# SensorModule.net
KiCad netlist of a schematic drawn in EAGLE
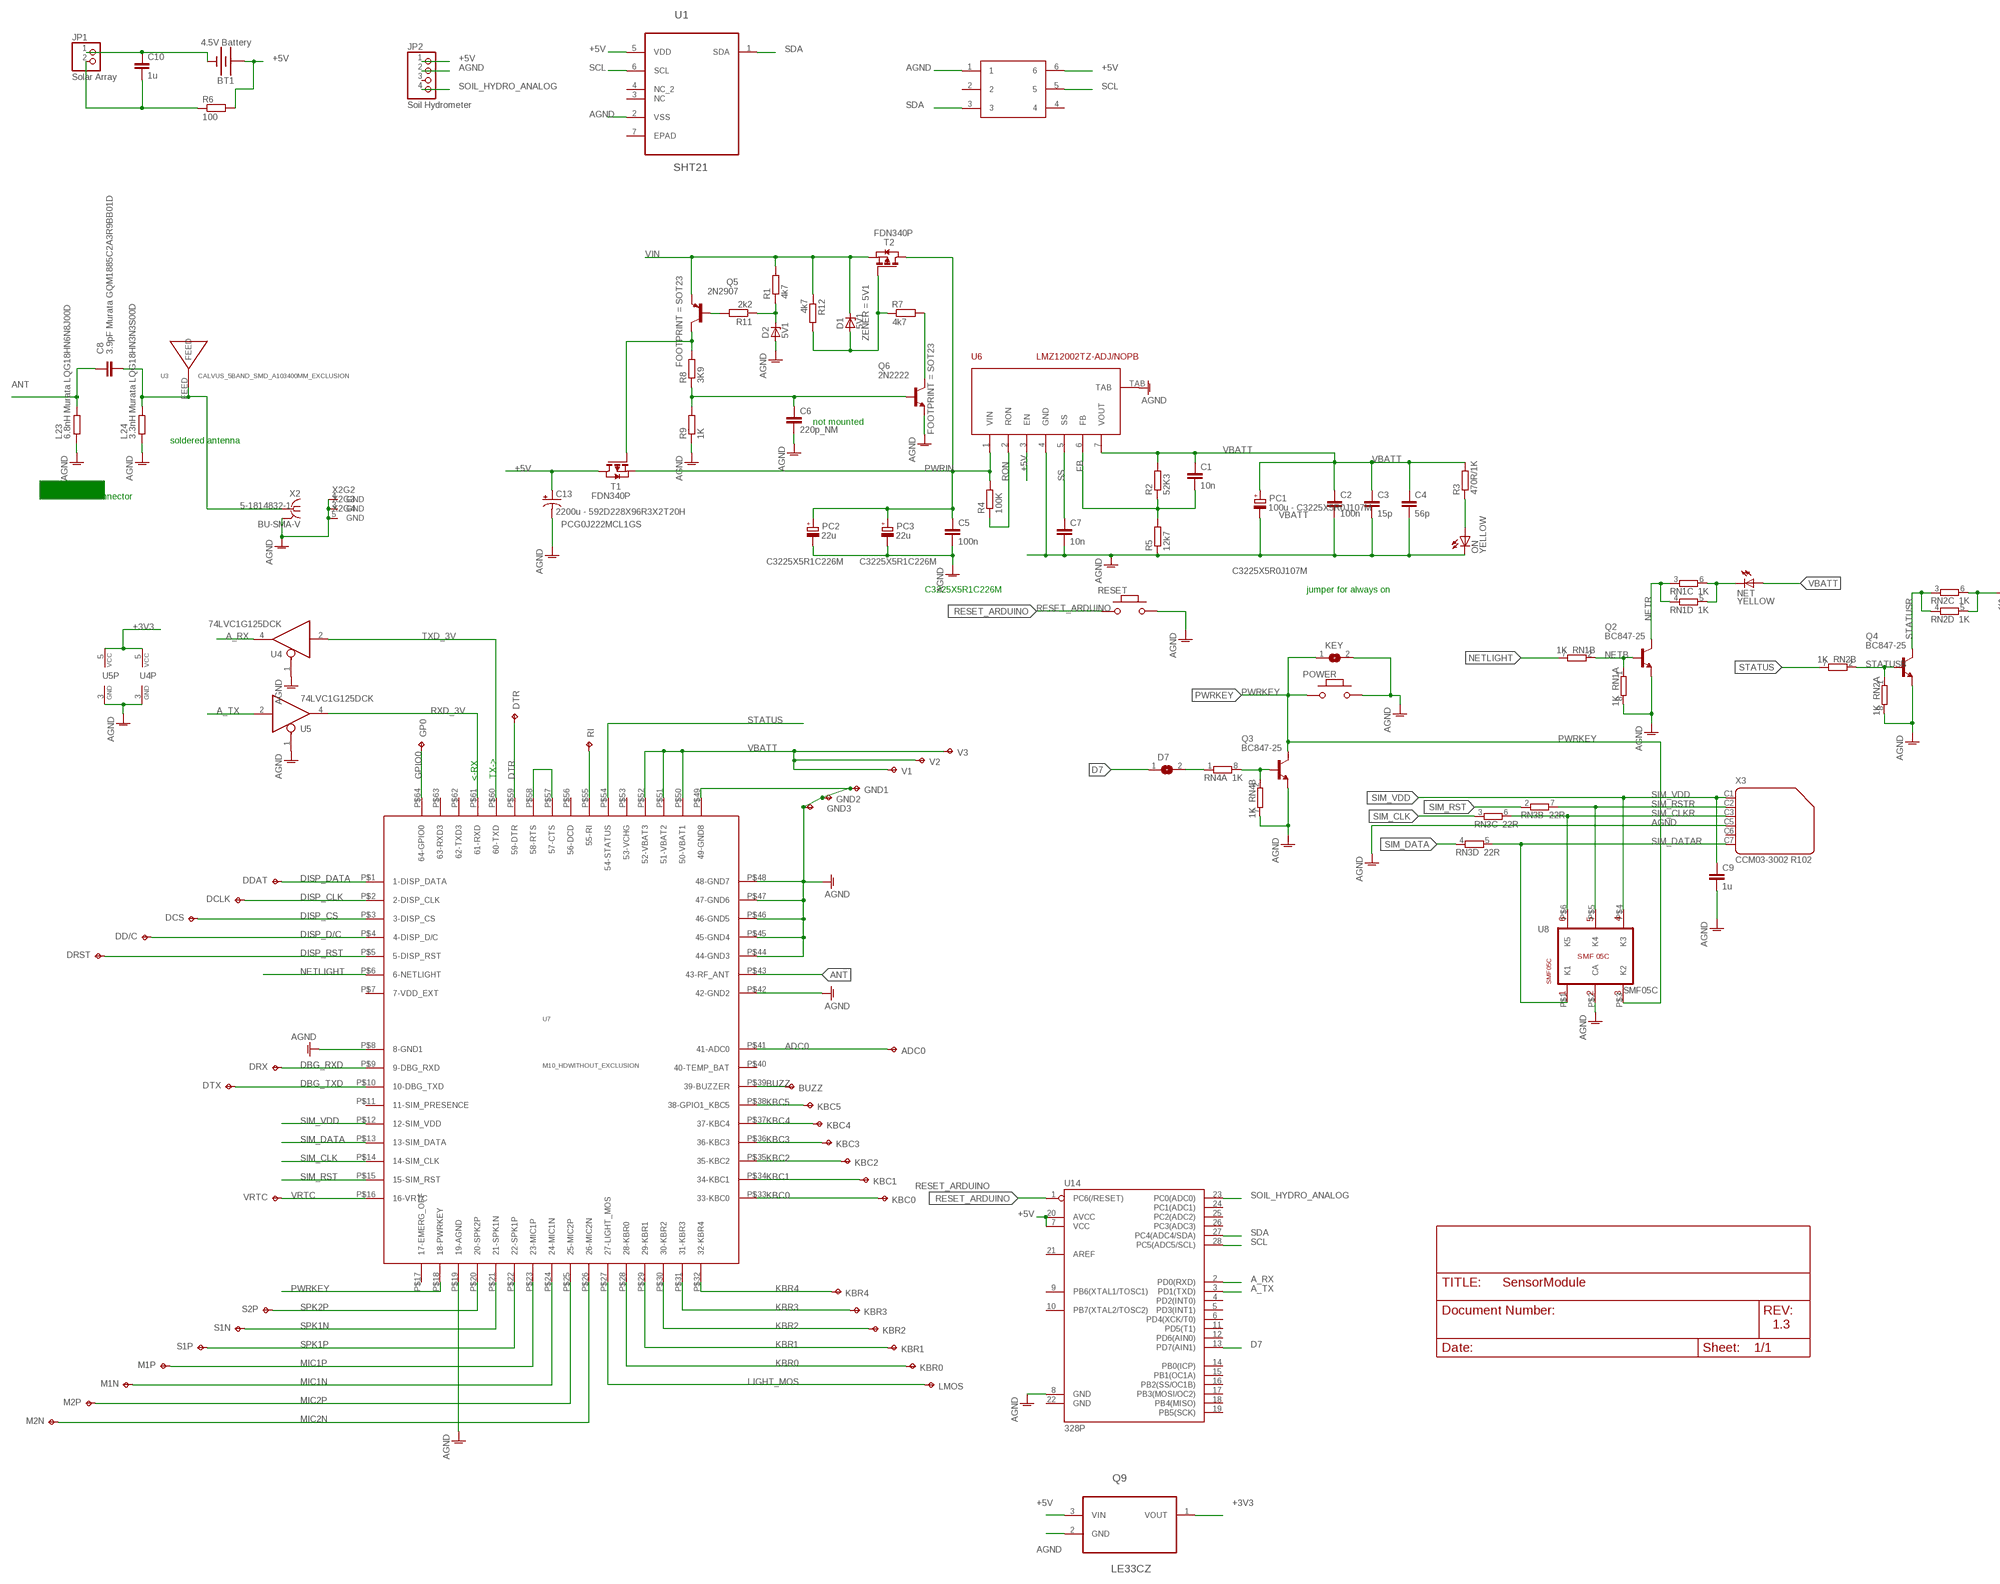
[diagram p0: schematic, sheet 1, part 1 of 2]
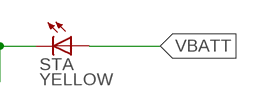
[diagram p1: schematic, sheet 1, part 2 of 2]

(export (version "E")
  (design (tool "Eeschema 10.0.6"))
  (components
    (comp (ref "ADC0")
      (value "TPPAD1-09")
      (footprint "eagle-import:P1-09")
      (libsource (lib "eagle-import") (part "TPPAD1-09"))
    )
    (comp (ref "BT1")
      (value "4.5V Battery")
      (footprint "eagle-import:BATTERY-AA")
      (libsource (lib "eagle-import") (part "BATTERY-AA"))
    )
    (comp (ref "BUZZ")
      (value "TPPAD1-09")
      (footprint "eagle-import:P1-09")
      (libsource (lib "eagle-import") (part "TPPAD1-09"))
    )
    (comp (ref "C1")
      (value "10n")
      (footprint "eagle-import:C0603-ROUND")
      (libsource (lib "eagle-import") (part "C-EU0603-RND"))
    )
    (comp (ref "C2")
      (value "100n")
      (footprint "eagle-import:C0603-ROUND")
      (libsource (lib "eagle-import") (part "C-EU0603-RND"))
    )
    (comp (ref "C3")
      (value "15p")
      (footprint "eagle-import:C0603-ROUND")
      (libsource (lib "eagle-import") (part "C-EU0603-RND"))
    )
    (comp (ref "C4")
      (value "56p")
      (footprint "eagle-import:C0603-ROUND")
      (libsource (lib "eagle-import") (part "C-EU0603-RND"))
    )
    (comp (ref "C5")
      (value "100n")
      (footprint "eagle-import:C0603-ROUND")
      (libsource (lib "eagle-import") (part "C-EU0603-RND"))
    )
    (comp (ref "C6")
      (value "220p_NM")
      (footprint "eagle-import:C0603-ROUND")
      (libsource (lib "eagle-import") (part "C-EU0603-RND"))
    )
    (comp (ref "C7")
      (value "10n")
      (footprint "eagle-import:C0603-ROUND")
      (libsource (lib "eagle-import") (part "C-EU0603-RND"))
    )
    (comp (ref "C8")
      (value "3.9pF Murata GQM1885C2A3R9BB01D")
      (footprint "eagle-import:C0603-ROUND")
      (libsource (lib "eagle-import") (part "C-EU0603-RND"))
    )
    (comp (ref "C9")
      (value "1u")
      (footprint "eagle-import:C0603-ROUND")
      (libsource (lib "eagle-import") (part "C-EU0603-RND"))
    )
    (comp (ref "C10")
      (value "1u")
      (footprint "eagle-import:C0201")
      (libsource (lib "eagle-import") (part "resistor_C-EUC0201"))
    )
    (comp (ref "C13")
      (value "2200u - 592D228X96R3X2T20H")
      (footprint "eagle-import:085CS_1AW")
      (libsource (lib "eagle-import") (part "CPOL-US085CS-1AW"))
    )
    (comp (ref "D1")
      (value "5V1")
      (footprint "eagle-import:SMB")
      (fields (field (name "ZENER") "5V1"))
      (libsource (lib "eagle-import") (part "ZENER-DIODESMB"))
    )
    (comp (ref "D2")
      (value "5V1")
      (footprint "eagle-import:SMB")
      (libsource (lib "eagle-import") (part "ZENER-DIODESMB"))
    )
    (comp (ref "D7") (value "SJ") (footprint "eagle-import:SJ") (libsource (lib "eagle-import") (part "SJ")))
    (comp (ref "DCLK")
      (value "TPPAD1-09")
      (footprint "eagle-import:P1-09")
      (libsource (lib "eagle-import") (part "TPPAD1-09"))
    )
    (comp (ref "DCS")
      (value "TPPAD1-09")
      (footprint "eagle-import:P1-09")
      (libsource (lib "eagle-import") (part "TPPAD1-09"))
    )
    (comp (ref "DD/C")
      (value "TPPAD1-09")
      (footprint "eagle-import:P1-09")
      (libsource (lib "eagle-import") (part "TPPAD1-09"))
    )
    (comp (ref "DDAT")
      (value "TPPAD1-09")
      (footprint "eagle-import:P1-09")
      (libsource (lib "eagle-import") (part "TPPAD1-09"))
    )
    (comp (ref "DRST")
      (value "TPPAD1-09")
      (footprint "eagle-import:P1-09")
      (libsource (lib "eagle-import") (part "TPPAD1-09"))
    )
    (comp (ref "DRX")
      (value "TPPAD1-09")
      (footprint "eagle-import:P1-09")
      (libsource (lib "eagle-import") (part "TPPAD1-09"))
    )
    (comp (ref "DTR")
      (value "TPPAD1-09")
      (footprint "eagle-import:P1-09")
      (libsource (lib "eagle-import") (part "TPPAD1-09"))
    )
    (comp (ref "DTX")
      (value "TPPAD1-09")
      (footprint "eagle-import:P1-09")
      (libsource (lib "eagle-import") (part "TPPAD1-09"))
    )
    (comp (ref "GND1")
      (value "TPPAD1-09")
      (footprint "eagle-import:P1-09")
      (libsource (lib "eagle-import") (part "TPPAD1-09"))
    )
    (comp (ref "GND2")
      (value "TPPAD1-09")
      (footprint "eagle-import:P1-09")
      (libsource (lib "eagle-import") (part "TPPAD1-09"))
    )
    (comp (ref "GND3")
      (value "TPPAD1-09")
      (footprint "eagle-import:P1-09")
      (libsource (lib "eagle-import") (part "TPPAD1-09"))
    )
    (comp (ref "GP0")
      (value "TPPAD1-09")
      (footprint "eagle-import:P1-09")
      (libsource (lib "eagle-import") (part "TPPAD1-09"))
    )
    (comp (ref "JP1")
      (value "Solar Array")
      (footprint "eagle-import:1X02")
      (libsource (lib "eagle-import") (part "PINHD-1X2"))
    )
    (comp (ref "JP2")
      (value "Soil Hydrometer")
      (footprint "eagle-import:1X04")
      (libsource (lib "eagle-import") (part "PINHD-1X4"))
    )
    (comp (ref "KBC0")
      (value "TPPAD1-09")
      (footprint "eagle-import:P1-09")
      (libsource (lib "eagle-import") (part "TPPAD1-09"))
    )
    (comp (ref "KBC1")
      (value "TPPAD1-09")
      (footprint "eagle-import:P1-09")
      (libsource (lib "eagle-import") (part "TPPAD1-09"))
    )
    (comp (ref "KBC2")
      (value "TPPAD1-09")
      (footprint "eagle-import:P1-09")
      (libsource (lib "eagle-import") (part "TPPAD1-09"))
    )
    (comp (ref "KBC3")
      (value "TPPAD1-09")
      (footprint "eagle-import:P1-09")
      (libsource (lib "eagle-import") (part "TPPAD1-09"))
    )
    (comp (ref "KBC4")
      (value "TPPAD1-09")
      (footprint "eagle-import:P1-09")
      (libsource (lib "eagle-import") (part "TPPAD1-09"))
    )
    (comp (ref "KBC5")
      (value "TPPAD1-09")
      (footprint "eagle-import:P1-09")
      (libsource (lib "eagle-import") (part "TPPAD1-09"))
    )
    (comp (ref "KBR0")
      (value "TPPAD1-09")
      (footprint "eagle-import:P1-09")
      (libsource (lib "eagle-import") (part "TPPAD1-09"))
    )
    (comp (ref "KBR1")
      (value "TPPAD1-09")
      (footprint "eagle-import:P1-09")
      (libsource (lib "eagle-import") (part "TPPAD1-09"))
    )
    (comp (ref "KBR2")
      (value "TPPAD1-09")
      (footprint "eagle-import:P1-09")
      (libsource (lib "eagle-import") (part "TPPAD1-09"))
    )
    (comp (ref "KBR3")
      (value "TPPAD1-09")
      (footprint "eagle-import:P1-09")
      (libsource (lib "eagle-import") (part "TPPAD1-09"))
    )
    (comp (ref "KBR4")
      (value "TPPAD1-09")
      (footprint "eagle-import:P1-09")
      (libsource (lib "eagle-import") (part "TPPAD1-09"))
    )
    (comp (ref "KEY") (value "SJ") (footprint "eagle-import:SJ") (libsource (lib "eagle-import") (part "SJ")))
    (comp (ref "L23")
      (value "6.8nH Murata LQG18HN6N8J00D")
      (footprint "eagle-import:R0603-ROUND")
      (libsource (lib "eagle-import") (part "R-EU_0603-RND"))
    )
    (comp (ref "L24")
      (value "3.3nH Murata LQG18HN3N3S00D")
      (footprint "eagle-import:R0603-ROUND")
      (libsource (lib "eagle-import") (part "R-EU_0603-RND"))
    )
    (comp (ref "LMOS")
      (value "TPPAD1-09")
      (footprint "eagle-import:P1-09")
      (libsource (lib "eagle-import") (part "TPPAD1-09"))
    )
    (comp (ref "M1N")
      (value "TPPAD1-09")
      (footprint "eagle-import:P1-09")
      (libsource (lib "eagle-import") (part "TPPAD1-09"))
    )
    (comp (ref "M1P")
      (value "TPPAD1-09")
      (footprint "eagle-import:P1-09")
      (libsource (lib "eagle-import") (part "TPPAD1-09"))
    )
    (comp (ref "M2N")
      (value "TPPAD1-09")
      (footprint "eagle-import:P1-09")
      (libsource (lib "eagle-import") (part "TPPAD1-09"))
    )
    (comp (ref "M2P")
      (value "TPPAD1-09")
      (footprint "eagle-import:P1-09")
      (libsource (lib "eagle-import") (part "TPPAD1-09"))
    )
    (comp (ref "NET")
      (value "YELLOW")
      (footprint "eagle-import:CHIP-LED0805")
      (libsource (lib "eagle-import") (part "LEDCHIP-LED0805"))
    )
    (comp (ref "ON")
      (value "YELLOW")
      (footprint "eagle-import:CHIP-LED0805")
      (libsource (lib "eagle-import") (part "LEDCHIP-LED0805"))
    )
    (comp (ref "PC1")
      (value "100u - C3225X5R0J107M")
      (footprint "eagle-import:SMC_B")
      (fields (field (name "PN") "C3225X5R0J107M"))
      (libsource (lib "eagle-import") (part "CPOL-EUSMCB"))
    )
    (comp (ref "PC2")
      (value "22u")
      (footprint "eagle-import:SMC_B")
      (fields (field (name "PN") "C3225X5R1C226M "))
      (libsource (lib "eagle-import") (part "CPOL-EUSMCB"))
    )
    (comp (ref "PC3")
      (value "22u")
      (footprint "eagle-import:SMC_B")
      (fields (field (name "PN") "C3225X5R1C226M "))
      (libsource (lib "eagle-import") (part "CPOL-EUSMCB"))
    )
    (comp (ref "POWER")
      (value "MYSMD_PB157")
      (footprint "eagle-import:SMD_157SW")
      (libsource (lib "eagle-import") (part "MYSMD_PB157"))
    )
    (comp (ref "Q2")
      (value "BC847-25")
      (footprint "eagle-import:SOT23-BEC")
      (libsource (lib "eagle-import") (part "BC817SMD-25"))
    )
    (comp (ref "Q3")
      (value "BC847-25")
      (footprint "eagle-import:SOT23-BEC")
      (libsource (lib "eagle-import") (part "BC817SMD-25"))
    )
    (comp (ref "Q4")
      (value "BC847-25")
      (footprint "eagle-import:SOT23-BEC")
      (libsource (lib "eagle-import") (part "BC817SMD-25"))
    )
    (comp (ref "Q5")
      (value "2N2907")
      (footprint "SOT23")
      (libsource (lib "eagle-import") (part "-PNP-SOT23-BECMMBT2907ALT1"))
    )
    (comp (ref "Q6")
      (value "2N2222")
      (footprint "SOT23")
      (libsource (lib "eagle-import") (part "-NPN-SOT23-BECMMBT2222ALT1"))
    )
    (comp (ref "Q9")
      (value "LE33CZ")
      (footprint "eagle-import:TO127P254X749-3")
      (libsource (lib "eagle-import") (part "LE33CZ"))
    )
    (comp (ref "R1")
      (value "4k7")
      (footprint "eagle-import:R0603-ROUND")
      (libsource (lib "eagle-import") (part "R-EU_0603-RND"))
    )
    (comp (ref "R2")
      (value "52K3")
      (footprint "eagle-import:R0603-ROUND")
      (libsource (lib "eagle-import") (part "R-EU_0603-RND"))
    )
    (comp (ref "R3")
      (value "470R/1K")
      (footprint "eagle-import:R0603-ROUND")
      (libsource (lib "eagle-import") (part "R-EU_0603-RND"))
    )
    (comp (ref "R4")
      (value "100K")
      (footprint "eagle-import:R0603-ROUND")
      (libsource (lib "eagle-import") (part "R-EU_0603-RND"))
    )
    (comp (ref "R5")
      (value "12k7")
      (footprint "eagle-import:R0603-ROUND")
      (libsource (lib "eagle-import") (part "R-EU_0603-RND"))
    )
    (comp (ref "R6")
      (value "100")
      (footprint "eagle-import:R0201")
      (libsource (lib "eagle-import") (part "resistor_R-EU_R0201"))
    )
    (comp (ref "R7")
      (value "4k7")
      (footprint "eagle-import:R0603-ROUND")
      (libsource (lib "eagle-import") (part "R-EU_0603-RND"))
    )
    (comp (ref "R8")
      (value "3K9")
      (footprint "eagle-import:R0603-ROUND")
      (libsource (lib "eagle-import") (part "R-EU_0603-RND"))
    )
    (comp (ref "R9")
      (value "1K")
      (footprint "eagle-import:R0603-ROUND")
      (libsource (lib "eagle-import") (part "R-EU_0603-RND"))
    )
    (comp (ref "R11")
      (value "2k2")
      (footprint "eagle-import:R0603-ROUND")
      (libsource (lib "eagle-import") (part "R-EU_0603-RND"))
    )
    (comp (ref "R12")
      (value "4k7")
      (footprint "eagle-import:R0603-ROUND")
      (libsource (lib "eagle-import") (part "R-EU_0603-RND"))
    )
    (comp (ref "RESET")
      (value "MYSMD_PB157")
      (footprint "eagle-import:SMD_157SW")
      (libsource (lib "eagle-import") (part "MYSMD_PB157"))
    )
    (comp (ref "RI")
      (value "TPPAD1-09")
      (footprint "eagle-import:P1-09")
      (libsource (lib "eagle-import") (part "TPPAD1-09"))
    )
    (comp (ref "RN1")
      (value "1K")
      (footprint "eagle-import:CAY16")
      (libsource (lib "eagle-import") (part "4R-NCAY16"))
    )
    (comp (ref "RN2")
      (value "1K")
      (footprint "eagle-import:CAY16")
      (libsource (lib "eagle-import") (part "4R-NCAY16"))
    )
    (comp (ref "RN3")
      (value "22R")
      (footprint "eagle-import:CAY16")
      (libsource (lib "eagle-import") (part "4R-NCAY16"))
    )
    (comp (ref "RN4")
      (value "1K")
      (footprint "eagle-import:CAY16")
      (libsource (lib "eagle-import") (part "4R-NCAY16"))
    )
    (comp (ref "S1N")
      (value "TPPAD1-09")
      (footprint "eagle-import:P1-09")
      (libsource (lib "eagle-import") (part "TPPAD1-09"))
    )
    (comp (ref "S1P")
      (value "TPPAD1-09")
      (footprint "eagle-import:P1-09")
      (libsource (lib "eagle-import") (part "TPPAD1-09"))
    )
    (comp (ref "S2P")
      (value "TPPAD1-09")
      (footprint "eagle-import:P1-09")
      (libsource (lib "eagle-import") (part "TPPAD1-09"))
    )
    (comp (ref "STA")
      (value "YELLOW")
      (footprint "eagle-import:CHIP-LED0805")
      (libsource (lib "eagle-import") (part "LEDCHIP-LED0805"))
    )
    (comp (ref "T1")
      (value "FDN340P")
      (footprint "eagle-import:SOT-23")
      (libsource (lib "eagle-import") (part "PMOSSOT23"))
    )
    (comp (ref "T2")
      (value "FDN340P")
      (footprint "eagle-import:SOT-23")
      (libsource (lib "eagle-import") (part "PMOSSOT23"))
    )
    (comp (ref "U$1")
      (value "VISHAY_VEML6070")
      (footprint "eagle-import:SOT-23-6")
      (libsource (lib "eagle-import") (part "VISHAY_VEML6070"))
    )
    (comp (ref "U1")
      (value "SHT21")
      (footprint "eagle-import:DFN300X300X110-7N")
      (libsource (lib "eagle-import") (part "SHT21"))
    )
    (comp (ref "U3")
      (value "CALVUS_5BAND_SMD_A103400MM_EXCLUSION")
      (footprint "eagle-import:CALVUS_5BAND_SMD_A10340_0MM_EXCLUSION")
      (libsource (lib "eagle-import") (part "CALVUS_5BAND_SMD_A103400MM_EXCLUSION"))
    )
    (comp (ref "U4")
      (value "74LVC1G125DCK")
      (footprint "eagle-import:SC70-5")
      (libsource (lib "eagle-import") (part "741G125DCKLVC"))
    )
    (comp (ref "U5")
      (value "74LVC1G125DCK")
      (footprint "eagle-import:SC70-5")
      (libsource (lib "eagle-import") (part "741G125DCKLVC"))
    )
    (comp (ref "U6")
      (value "LMZ12002TZ-ADJ/NOPB")
      (footprint "eagle-import:TZA-7")
      (libsource (lib "eagle-import") (part "LMZ1200X"))
    )
    (comp (ref "U7")
      (value "M10_HDWITHOUT_EXCLUSION")
      (footprint "eagle-import:M10_HD_WITHOUT_EXCLUSION")
      (libsource (lib "eagle-import") (part "M10_HDWITHOUT_EXCLUSION"))
    )
    (comp (ref "U8")
      (value "SMF05C")
      (footprint "eagle-import:SC70_6L")
      (libsource (lib "eagle-import") (part "SMF05C"))
    )
    (comp (ref "U14")
      (value "328P")
      (footprint "eagle-import:DIP28")
      (libsource (lib "eagle-import") (part "ATMEGA328P_PDIP"))
    )
    (comp (ref "V1")
      (value "TPPAD1-09")
      (footprint "eagle-import:P1-09")
      (libsource (lib "eagle-import") (part "TPPAD1-09"))
    )
    (comp (ref "V2")
      (value "TPPAD1-09")
      (footprint "eagle-import:P1-09")
      (libsource (lib "eagle-import") (part "TPPAD1-09"))
    )
    (comp (ref "V3")
      (value "TPPAD1-09")
      (footprint "eagle-import:P1-09")
      (libsource (lib "eagle-import") (part "TPPAD1-09"))
    )
    (comp (ref "VRTC")
      (value "TPPAD1-09")
      (footprint "eagle-import:P1-09")
      (libsource (lib "eagle-import") (part "TPPAD1-09"))
    )
    (comp (ref "X2")
      (value "BU-SMA-V")
      (footprint "eagle-import:BU-SMA-V")
      (fields (field (name "PN") "5-1814832-1"))
      (libsource (lib "eagle-import") (part "BU-SMA-V"))
    )
    (comp (ref "X3")
      (value "CCM03-3002 R102")
      (footprint "eagle-import:CON-AMPHENOL_C707_10M006_512_2")
      (fields (field (name "OC_FARNELL") "1463072 "))
      (libsource (lib "eagle-import") (part "CON-AMPHENOL_SIMLOCK-C707_10M006_512_2"))
    )
  )
  (nets
    (net (code "1") (name "/+3V3") (class "Default")
      (node (ref "Q9") (pin "1") (pinfunction "VOUT_1") (pintype "output"))
      (node (ref "U4") (pin "5") (pinfunction "VCC_5") (pintype "power_in"))
      (node (ref "U5") (pin "5") (pinfunction "VCC_5") (pintype "power_in"))
    )
    (net (code "2") (name "/+5V") (class "Default")
      (node (ref "BT1") (pin "PWR@1") (pinfunction "+_PWR@1") (pintype "power_in"))
      (node (ref "C13") (pin "+") (pinfunction "+_+") (pintype "passive"))
      (node (ref "JP2") (pin "1") (pinfunction "1_1") (pintype "passive"))
      (node (ref "Q9") (pin "3") (pinfunction "VIN_3") (pintype "power_in"))
      (node (ref "R6") (pin "2") (pinfunction "2_2") (pintype "passive"))
      (node (ref "T1") (pin "1") (pinfunction "D_1") (pintype "passive"))
      (node (ref "U$1") (pin "6") (pinfunction "6_6") (pintype "bidirectional"))
      (node (ref "U1") (pin "5") (pinfunction "VDD_5") (pintype "power_in"))
      (node (ref "U14") (pin "20") (pinfunction "AVCC_20") (pintype "bidirectional"))
      (node (ref "U14") (pin "7") (pinfunction "VCC_7") (pintype "bidirectional"))
      (node (ref "U6") (pin "3") (pinfunction "EN_3") (pintype "input"))
    )
    (net (code "3") (name "/ADC0") (class "Default")
      (node (ref "ADC0") (pin "TP") (pinfunction "TP_TP") (pintype "input"))
      (node (ref "U7") (pin "P$41") (pinfunction "41-ADC0_P$41") (pintype "bidirectional"))
    )
    (net (code "4") (name "/A_RX") (class "Default")
      (node (ref "U14") (pin "2") (pinfunction "PD0(RXD)_2") (pintype "bidirectional"))
      (node (ref "U4") (pin "4") (pinfunction "O_4") (pintype "tri_state"))
    )
    (net (code "5") (name "/A_TX") (class "Default")
      (node (ref "U14") (pin "3") (pinfunction "PD1(TXD)_3") (pintype "bidirectional"))
      (node (ref "U5") (pin "2") (pinfunction "I_2") (pintype "input"))
    )
    (net (code "6") (name "/BUZZ") (class "Default")
      (node (ref "BUZZ") (pin "TP") (pinfunction "TP_TP") (pintype "input"))
      (node (ref "U7") (pin "P$39") (pinfunction "39-BUZZER_P$39") (pintype "bidirectional"))
    )
    (net (code "7") (name "/DBG_RXD") (class "Default")
      (node (ref "DRX") (pin "TP") (pinfunction "TP_TP") (pintype "input"))
      (node (ref "U7") (pin "P$9") (pinfunction "9-DBG_RXD_P$9") (pintype "bidirectional"))
    )
    (net (code "8") (name "/DBG_TXD") (class "Default")
      (node (ref "DTX") (pin "TP") (pinfunction "TP_TP") (pintype "input"))
      (node (ref "U7") (pin "P$10") (pinfunction "10-DBG_TXD_P$10") (pintype "bidirectional"))
    )
    (net (code "9") (name "/DISP_CLK") (class "Default")
      (node (ref "DCLK") (pin "TP") (pinfunction "TP_TP") (pintype "input"))
      (node (ref "U7") (pin "P$2") (pinfunction "2-DISP_CLK_P$2") (pintype "bidirectional"))
    )
    (net (code "10") (name "/DISP_CS") (class "Default")
      (node (ref "DCS") (pin "TP") (pinfunction "TP_TP") (pintype "input"))
      (node (ref "U7") (pin "P$3") (pinfunction "3-DISP_CS_P$3") (pintype "bidirectional"))
    )
    (net (code "11") (name "/DISP_DATA") (class "Default")
      (node (ref "DDAT") (pin "TP") (pinfunction "TP_TP") (pintype "input"))
      (node (ref "U7") (pin "P$1") (pinfunction "1-DISP_DATA_P$1") (pintype "bidirectional"))
    )
    (net (code "12") (name "/DISP_D{slash}C") (class "Default")
      (node (ref "DD/C") (pin "TP") (pinfunction "TP_TP") (pintype "input"))
      (node (ref "U7") (pin "P$4") (pinfunction "4-DISP_D/C_P$4") (pintype "bidirectional"))
    )
    (net (code "13") (name "/DISP_RST") (class "Default")
      (node (ref "DRST") (pin "TP") (pinfunction "TP_TP") (pintype "input"))
      (node (ref "U7") (pin "P$5") (pinfunction "5-DISP_RST_P$5") (pintype "bidirectional"))
    )
    (net (code "14") (name "/DTR") (class "Default")
      (node (ref "DTR") (pin "TP") (pinfunction "TP_TP") (pintype "input"))
      (node (ref "U7") (pin "P$59") (pinfunction "59-DTR_P$59") (pintype "bidirectional"))
    )
    (net (code "15") (name "/FB") (class "Default")
      (node (ref "C1") (pin "2") (pinfunction "2_2") (pintype "passive"))
      (node (ref "R2") (pin "1") (pinfunction "1_1") (pintype "passive"))
      (node (ref "R5") (pin "2") (pinfunction "2_2") (pintype "passive"))
      (node (ref "U6") (pin "6") (pinfunction "FB_6") (pintype "input"))
    )
    (net (code "16") (name "/GPIO0") (class "Default")
      (node (ref "GP0") (pin "TP") (pinfunction "TP_TP") (pintype "input"))
      (node (ref "U7") (pin "P$64") (pinfunction "64-GPIO0_P$64") (pintype "bidirectional"))
    )
    (net (code "17") (name "/KBC0") (class "Default")
      (node (ref "KBC0") (pin "TP") (pinfunction "TP_TP") (pintype "input"))
      (node (ref "U7") (pin "P$33") (pinfunction "33-KBC0_P$33") (pintype "bidirectional"))
    )
    (net (code "18") (name "/KBC1") (class "Default")
      (node (ref "KBC1") (pin "TP") (pinfunction "TP_TP") (pintype "input"))
      (node (ref "U7") (pin "P$34") (pinfunction "34-KBC1_P$34") (pintype "bidirectional"))
    )
    (net (code "19") (name "/KBC2") (class "Default")
      (node (ref "KBC2") (pin "TP") (pinfunction "TP_TP") (pintype "input"))
      (node (ref "U7") (pin "P$35") (pinfunction "35-KBC2_P$35") (pintype "bidirectional"))
    )
    (net (code "20") (name "/KBC3") (class "Default")
      (node (ref "KBC3") (pin "TP") (pinfunction "TP_TP") (pintype "input"))
      (node (ref "U7") (pin "P$36") (pinfunction "36-KBC3_P$36") (pintype "bidirectional"))
    )
    (net (code "21") (name "/KBC4") (class "Default")
      (node (ref "KBC4") (pin "TP") (pinfunction "TP_TP") (pintype "input"))
      (node (ref "U7") (pin "P$37") (pinfunction "37-KBC4_P$37") (pintype "bidirectional"))
    )
    (net (code "22") (name "/KBC5") (class "Default")
      (node (ref "KBC5") (pin "TP") (pinfunction "TP_TP") (pintype "input"))
      (node (ref "U7") (pin "P$38") (pinfunction "38-GPIO1_KBC5_P$38") (pintype "bidirectional"))
    )
    (net (code "23") (name "/KBR0") (class "Default")
      (node (ref "KBR0") (pin "TP") (pinfunction "TP_TP") (pintype "input"))
      (node (ref "U7") (pin "P$28") (pinfunction "28-KBR0_P$28") (pintype "bidirectional"))
    )
    (net (code "24") (name "/KBR1") (class "Default")
      (node (ref "KBR1") (pin "TP") (pinfunction "TP_TP") (pintype "input"))
      (node (ref "U7") (pin "P$29") (pinfunction "29-KBR1_P$29") (pintype "bidirectional"))
    )
    (net (code "25") (name "/KBR2") (class "Default")
      (node (ref "KBR2") (pin "TP") (pinfunction "TP_TP") (pintype "input"))
      (node (ref "U7") (pin "P$30") (pinfunction "30-KBR2_P$30") (pintype "bidirectional"))
    )
    (net (code "26") (name "/KBR3") (class "Default")
      (node (ref "KBR3") (pin "TP") (pinfunction "TP_TP") (pintype "input"))
      (node (ref "U7") (pin "P$31") (pinfunction "31-KBR3_P$31") (pintype "bidirectional"))
    )
    (net (code "27") (name "/KBR4") (class "Default")
      (node (ref "KBR4") (pin "TP") (pinfunction "TP_TP") (pintype "input"))
      (node (ref "U7") (pin "P$32") (pinfunction "32-KBR4_P$32") (pintype "bidirectional"))
    )
    (net (code "28") (name "/LIGHT_MOS") (class "Default")
      (node (ref "LMOS") (pin "TP") (pinfunction "TP_TP") (pintype "input"))
      (node (ref "U7") (pin "P$27") (pinfunction "27-LIGHT_MOS_P$27") (pintype "bidirectional"))
    )
    (net (code "29") (name "/MIC1N") (class "Default")
      (node (ref "M1N") (pin "TP") (pinfunction "TP_TP") (pintype "input"))
      (node (ref "U7") (pin "P$24") (pinfunction "24-MIC1N_P$24") (pintype "bidirectional"))
    )
    (net (code "30") (name "/MIC1P") (class "Default")
      (node (ref "M1P") (pin "TP") (pinfunction "TP_TP") (pintype "input"))
      (node (ref "U7") (pin "P$23") (pinfunction "23-MIC1P_P$23") (pintype "bidirectional"))
    )
    (net (code "31") (name "/MIC2N") (class "Default")
      (node (ref "M2N") (pin "TP") (pinfunction "TP_TP") (pintype "input"))
      (node (ref "U7") (pin "P$26") (pinfunction "26-MIC2N_P$26") (pintype "bidirectional"))
    )
    (net (code "32") (name "/MIC2P") (class "Default")
      (node (ref "M2P") (pin "TP") (pinfunction "TP_TP") (pintype "input"))
      (node (ref "U7") (pin "P$25") (pinfunction "25-MIC2P_P$25") (pintype "bidirectional"))
    )
    (net (code "33") (name "/NETB") (class "Default")
      (node (ref "Q2") (pin "B") (pinfunction "B_B") (pintype "passive"))
      (node (ref "RN1") (pin "1") (pinfunction "1_1") (pintype "passive"))
      (node (ref "RN1") (pin "2") (pinfunction "1_2") (pintype "passive"))
    )
    (net (code "34") (name "/NETR") (class "Default")
      (node (ref "Q2") (pin "C") (pinfunction "C_C") (pintype "passive"))
      (node (ref "RN1") (pin "3") (pinfunction "1_3") (pintype "passive"))
      (node (ref "RN1") (pin "4") (pinfunction "1_4") (pintype "passive"))
    )
    (net (code "35") (name "/PWRIN") (class "Default")
      (node (ref "C5") (pin "1") (pinfunction "1_1") (pintype "passive"))
      (node (ref "PC2") (pin "+") (pinfunction "+_+") (pintype "passive"))
      (node (ref "PC3") (pin "+") (pinfunction "+_+") (pintype "passive"))
      (node (ref "R4") (pin "2") (pinfunction "2_2") (pintype "passive"))
      (node (ref "T1") (pin "2") (pinfunction "S_2") (pintype "passive"))
      (node (ref "T2") (pin "1") (pinfunction "D_1") (pintype "passive"))
      (node (ref "U6") (pin "1") (pinfunction "VIN_1") (pintype "input"))
    )
    (net (code "36") (name "/RON") (class "Default")
      (node (ref "R4") (pin "1") (pinfunction "1_1") (pintype "passive"))
      (node (ref "U6") (pin "2") (pinfunction "RON_2") (pintype "passive"))
    )
    (net (code "37") (name "/RXD_3V") (class "Default")
      (node (ref "U5") (pin "4") (pinfunction "O_4") (pintype "tri_state"))
      (node (ref "U7") (pin "P$61") (pinfunction "61-RXD_P$61") (pintype "bidirectional"))
    )
    (net (code "38") (name "/SCL") (class "Default")
      (node (ref "U$1") (pin "5") (pinfunction "5_5") (pintype "bidirectional"))
      (node (ref "U1") (pin "6") (pinfunction "SCL_6") (pintype "input"))
      (node (ref "U14") (pin "28") (pinfunction "PC5(ADC5/SCL)_28") (pintype "bidirectional"))
    )
    (net (code "39") (name "/SDA") (class "Default")
      (node (ref "U$1") (pin "3") (pinfunction "3_3") (pintype "bidirectional"))
      (node (ref "U1") (pin "1") (pinfunction "SDA_1") (pintype "bidirectional"))
      (node (ref "U14") (pin "27") (pinfunction "PC4(ADC4/SDA)_27") (pintype "bidirectional"))
    )
    (net (code "40") (name "/SIM_CLKR") (class "Default")
      (node (ref "RN3") (pin "6") (pinfunction "2_6") (pintype "passive"))
      (node (ref "U8") (pin "P$6") (pinfunction "K5_P$6") (pintype "bidirectional"))
      (node (ref "X3") (pin "C3") (pinfunction "3_C3") (pintype "passive"))
    )
    (net (code "41") (name "/SIM_DATAR") (class "Default")
      (node (ref "RN3") (pin "5") (pinfunction "2_5") (pintype "passive"))
      (node (ref "U8") (pin "P$1") (pinfunction "K1_P$1") (pintype "bidirectional"))
      (node (ref "X3") (pin "C7") (pinfunction "6_C7") (pintype "passive"))
    )
    (net (code "42") (name "/SIM_RSTR") (class "Default")
      (node (ref "RN3") (pin "7") (pinfunction "2_7") (pintype "passive"))
      (node (ref "U8") (pin "P$5") (pinfunction "K4_P$5") (pintype "bidirectional"))
      (node (ref "X3") (pin "C2") (pinfunction "2_C2") (pintype "passive"))
    )
    (net (code "43") (name "/SOIL_HYDRO_ANALOG") (class "Default")
      (node (ref "JP2") (pin "4") (pinfunction "4_4") (pintype "passive"))
      (node (ref "U14") (pin "23") (pinfunction "PC0(ADC0)_23") (pintype "bidirectional"))
    )
    (net (code "44") (name "/SPK1N") (class "Default")
      (node (ref "S1N") (pin "TP") (pinfunction "TP_TP") (pintype "input"))
      (node (ref "U7") (pin "P$21") (pinfunction "21-SPK1N_P$21") (pintype "bidirectional"))
    )
    (net (code "45") (name "/SPK1P") (class "Default")
      (node (ref "S1P") (pin "TP") (pinfunction "TP_TP") (pintype "input"))
      (node (ref "U7") (pin "P$22") (pinfunction "22-SPK1P_P$22") (pintype "bidirectional"))
    )
    (net (code "46") (name "/SPK2P") (class "Default")
      (node (ref "S2P") (pin "TP") (pinfunction "TP_TP") (pintype "input"))
      (node (ref "U7") (pin "P$20") (pinfunction "20-SPK2P_P$20") (pintype "bidirectional"))
    )
    (net (code "47") (name "/SS") (class "Default")
      (node (ref "C7") (pin "1") (pinfunction "1_1") (pintype "passive"))
      (node (ref "U6") (pin "5") (pinfunction "SS_5") (pintype "passive"))
    )
    (net (code "48") (name "/STATUSB") (class "Default")
      (node (ref "Q4") (pin "B") (pinfunction "B_B") (pintype "passive"))
      (node (ref "RN2") (pin "1") (pinfunction "1_1") (pintype "passive"))
      (node (ref "RN2") (pin "2") (pinfunction "1_2") (pintype "passive"))
    )
    (net (code "49") (name "/STATUSR") (class "Default")
      (node (ref "Q4") (pin "C") (pinfunction "C_C") (pintype "passive"))
      (node (ref "RN2") (pin "3") (pinfunction "1_3") (pintype "passive"))
      (node (ref "RN2") (pin "4") (pinfunction "1_4") (pintype "passive"))
    )
    (net (code "50") (name "/TXD_3V") (class "Default")
      (node (ref "U4") (pin "2") (pinfunction "I_2") (pintype "input"))
      (node (ref "U7") (pin "P$60") (pinfunction "60-TXD_P$60") (pintype "bidirectional"))
    )
    (net (code "51") (name "/VIN") (class "Default")
      (node (ref "D1") (pin "C") (pinfunction "C_C") (pintype "passive"))
      (node (ref "Q5") (pin "E") (pinfunction "E_E") (pintype "passive"))
      (node (ref "R1") (pin "2") (pinfunction "2_2") (pintype "passive"))
      (node (ref "R12") (pin "1") (pinfunction "1_1") (pintype "passive"))
      (node (ref "T2") (pin "2") (pinfunction "S_2") (pintype "passive"))
    )
    (net (code "52") (name "/VRTC") (class "Default")
      (node (ref "U7") (pin "P$16") (pinfunction "16-VRTC_P$16") (pintype "bidirectional"))
      (node (ref "VRTC") (pin "TP") (pinfunction "TP_TP") (pintype "input"))
    )
    (net (code "53") (name "AGND") (class "Default")
      (node (ref "BT1") (pin "GND@1") (pinfunction "-_GND@1") (pintype "power_in"))
      (node (ref "C10") (pin "1") (pinfunction "1_1") (pintype "passive"))
      (node (ref "C13") (pin "-") (pinfunction "-_-") (pintype "passive"))
      (node (ref "C2") (pin "2") (pinfunction "2_2") (pintype "passive"))
      (node (ref "C3") (pin "2") (pinfunction "2_2") (pintype "passive"))
      (node (ref "C4") (pin "2") (pinfunction "2_2") (pintype "passive"))
      (node (ref "C5") (pin "2") (pinfunction "2_2") (pintype "passive"))
      (node (ref "C6") (pin "2") (pinfunction "2_2") (pintype "passive"))
      (node (ref "C7") (pin "2") (pinfunction "2_2") (pintype "passive"))
      (node (ref "C9") (pin "2") (pinfunction "2_2") (pintype "passive"))
      (node (ref "D2") (pin "A") (pinfunction "A_A") (pintype "passive"))
      (node (ref "GND1") (pin "TP") (pinfunction "TP_TP") (pintype "input"))
      (node (ref "GND2") (pin "TP") (pinfunction "TP_TP") (pintype "input"))
      (node (ref "GND3") (pin "TP") (pinfunction "TP_TP") (pintype "input"))
      (node (ref "JP1") (pin "1") (pinfunction "1_1") (pintype "passive"))
      (node (ref "JP2") (pin "2") (pinfunction "2_2") (pintype "passive"))
      (node (ref "KEY") (pin "2") (pinfunction "2_2") (pintype "passive"))
      (node (ref "L23") (pin "1") (pinfunction "1_1") (pintype "passive"))
      (node (ref "L24") (pin "1") (pinfunction "1_1") (pintype "passive"))
      (node (ref "ON") (pin "C") (pinfunction "C_C") (pintype "passive"))
      (node (ref "PC1") (pin "-") (pinfunction "-_-") (pintype "passive"))
      (node (ref "PC2") (pin "-") (pinfunction "-_-") (pintype "passive"))
      (node (ref "PC3") (pin "-") (pinfunction "-_-") (pintype "passive"))
      (node (ref "POWER") (pin "2") (pinfunction "2_2") (pintype "passive"))
      (node (ref "Q2") (pin "E") (pinfunction "E_E") (pintype "passive"))
      (node (ref "Q3") (pin "E") (pinfunction "E_E") (pintype "passive"))
      (node (ref "Q4") (pin "E") (pinfunction "E_E") (pintype "passive"))
      (node (ref "Q6") (pin "E") (pinfunction "E_E") (pintype "passive"))
      (node (ref "Q9") (pin "2") (pinfunction "GND_2") (pintype "passive"))
      (node (ref "R5") (pin "1") (pinfunction "1_1") (pintype "passive"))
      (node (ref "R9") (pin "1") (pinfunction "1_1") (pintype "passive"))
      (node (ref "RESET") (pin "2") (pinfunction "2_2") (pintype "passive"))
      (node (ref "RN1") (pin "8") (pinfunction "2_8") (pintype "passive"))
      (node (ref "RN2") (pin "8") (pinfunction "2_8") (pintype "passive"))
      (node (ref "RN4") (pin "7") (pinfunction "2_7") (pintype "passive"))
      (node (ref "U$1") (pin "1") (pinfunction "1_1") (pintype "bidirectional"))
      (node (ref "U1") (pin "2") (pinfunction "VSS_2") (pintype "power_in"))
      (node (ref "U14") (pin "8") (pinfunction "GND_8") (pintype "bidirectional"))
      (node (ref "U4") (pin "1") (pinfunction "OE_1") (pintype "input"))
      (node (ref "U4") (pin "3") (pinfunction "GND_3") (pintype "power_in"))
      (node (ref "U5") (pin "1") (pinfunction "OE_1") (pintype "input"))
      (node (ref "U5") (pin "3") (pinfunction "GND_3") (pintype "power_in"))
      (node (ref "U6") (pin "4") (pinfunction "GND_4") (pintype "power_in"))
      (node (ref "U6") (pin "TAB") (pinfunction "TAB_TAB") (pintype "power_in"))
      (node (ref "U7") (pin "P$19") (pinfunction "19-AGND_P$19") (pintype "bidirectional"))
      (node (ref "U7") (pin "P$42") (pinfunction "42-GND2_P$42") (pintype "bidirectional"))
      (node (ref "U7") (pin "P$44") (pinfunction "44-GND3_P$44") (pintype "bidirectional"))
      (node (ref "U7") (pin "P$45") (pinfunction "45-GND4_P$45") (pintype "bidirectional"))
      (node (ref "U7") (pin "P$46") (pinfunction "46-GND5_P$46") (pintype "bidirectional"))
      (node (ref "U7") (pin "P$47") (pinfunction "47-GND6_P$47") (pintype "bidirectional"))
      (node (ref "U7") (pin "P$48") (pinfunction "48-GND7_P$48") (pintype "bidirectional"))
      (node (ref "U7") (pin "P$49") (pinfunction "49-GND8_P$49") (pintype "bidirectional"))
      (node (ref "U7") (pin "P$8") (pinfunction "8-GND1_P$8") (pintype "bidirectional"))
      (node (ref "U8") (pin "P$2") (pinfunction "CA_P$2") (pintype "bidirectional"))
      (node (ref "X2") (pin "2") (pinfunction "GND_2") (pintype "power_in"))
      (node (ref "X2") (pin "3") (pinfunction "GND_3") (pintype "power_in"))
      (node (ref "X2") (pin "4") (pinfunction "GND_4") (pintype "power_in"))
      (node (ref "X2") (pin "5") (pinfunction "GND_5") (pintype "power_in"))
      (node (ref "X3") (pin "C5") (pinfunction "4_C5") (pintype "passive"))
    )
    (net (code "54") (name "ANT") (class "Default")
      (node (ref "C8") (pin "1") (pinfunction "1_1") (pintype "passive"))
      (node (ref "L23") (pin "2") (pinfunction "2_2") (pintype "passive"))
      (node (ref "U7") (pin "P$43") (pinfunction "43-RF_ANT_P$43") (pintype "bidirectional"))
    )
    (net (code "55") (name "D7") (class "Default")
      (node (ref "D7") (pin "1") (pinfunction "1_1") (pintype "passive"))
      (node (ref "U14") (pin "13") (pinfunction "PD7(AIN1)_13") (pintype "bidirectional"))
    )
    (net (code "56") (name "NETLIGHT") (class "Default")
      (node (ref "RN1") (pin "7") (pinfunction "2_7") (pintype "passive"))
      (node (ref "U7") (pin "P$6") (pinfunction "6-NETLIGHT_P$6") (pintype "bidirectional"))
    )
    (net (code "57") (name "Net-(C6-Pad1)") (class "Default")
      (node (ref "C6") (pin "1") (pinfunction "1_1") (pintype "passive"))
      (node (ref "Q6") (pin "B") (pinfunction "B_B") (pintype "passive"))
      (node (ref "R8") (pin "1") (pinfunction "1_1") (pintype "passive"))
      (node (ref "R9") (pin "2") (pinfunction "2_2") (pintype "passive"))
    )
    (net (code "58") (name "Net-(C8-Pad2)") (class "Default")
      (node (ref "C8") (pin "2") (pinfunction "2_2") (pintype "passive"))
      (node (ref "L24") (pin "2") (pinfunction "2_2") (pintype "passive"))
      (node (ref "U3") (pin "FEED") (pinfunction "FEED_FEED") (pintype "bidirectional"))
      (node (ref "X2") (pin "1") (pinfunction "1_1") (pintype "passive"))
    )
    (net (code "59") (name "Net-(C10-Pad2)") (class "Default")
      (node (ref "C10") (pin "2") (pinfunction "2_2") (pintype "passive"))
      (node (ref "JP1") (pin "2") (pinfunction "2_2") (pintype "passive"))
      (node (ref "R6") (pin "1") (pinfunction "1_1") (pintype "passive"))
    )
    (net (code "60") (name "Net-(D2-PadC)") (class "Default")
      (node (ref "D2") (pin "C") (pinfunction "C_C") (pintype "passive"))
      (node (ref "R1") (pin "1") (pinfunction "1_1") (pintype "passive"))
      (node (ref "R11") (pin "1") (pinfunction "1_1") (pintype "passive"))
    )
    (net (code "61") (name "Net-(D7-Pad2)") (class "Default")
      (node (ref "D7") (pin "2") (pinfunction "2_2") (pintype "passive"))
      (node (ref "RN4") (pin "1") (pinfunction "1_1") (pintype "passive"))
    )
    (net (code "62") (name "Net-(ON-PadA)") (class "Default")
      (node (ref "ON") (pin "A") (pinfunction "A_A") (pintype "passive"))
      (node (ref "R3") (pin "1") (pinfunction "1_1") (pintype "passive"))
    )
    (net (code "63") (name "Net-(Q5-PadB)") (class "Default")
      (node (ref "Q5") (pin "B") (pinfunction "B_B") (pintype "passive"))
      (node (ref "R11") (pin "2") (pinfunction "2_2") (pintype "passive"))
    )
    (net (code "64") (name "Net-(Q6-PadC)") (class "Default")
      (node (ref "Q6") (pin "C") (pinfunction "C_C") (pintype "passive"))
      (node (ref "R7") (pin "2") (pinfunction "2_2") (pintype "passive"))
    )
    (net (code "65") (name "Net-(RN1C-2)") (class "Default")
      (node (ref "NET") (pin "C") (pinfunction "C_C") (pintype "passive"))
      (node (ref "RN1") (pin "5") (pinfunction "2_5") (pintype "passive"))
      (node (ref "RN1") (pin "6") (pinfunction "2_6") (pintype "passive"))
    )
    (net (code "66") (name "Net-(RN2C-2)") (class "Default")
      (node (ref "RN2") (pin "5") (pinfunction "2_5") (pintype "passive"))
      (node (ref "RN2") (pin "6") (pinfunction "2_6") (pintype "passive"))
      (node (ref "STA") (pin "C") (pinfunction "C_C") (pintype "passive"))
    )
    (net (code "67") (name "Net-(RN4A-2)") (class "Default")
      (node (ref "Q3") (pin "B") (pinfunction "B_B") (pintype "passive"))
      (node (ref "RN4") (pin "2") (pinfunction "1_2") (pintype "passive"))
      (node (ref "RN4") (pin "8") (pinfunction "2_8") (pintype "passive"))
    )
    (net (code "68") (name "Net-(T1-G)") (class "Default")
      (node (ref "Q5") (pin "C") (pinfunction "C_C") (pintype "passive"))
      (node (ref "R8") (pin "2") (pinfunction "2_2") (pintype "passive"))
      (node (ref "T1") (pin "3") (pinfunction "G_3") (pintype "passive"))
    )
    (net (code "69") (name "Net-(T2-G)") (class "Default")
      (node (ref "D1") (pin "A") (pinfunction "A_A") (pintype "passive"))
      (node (ref "R12") (pin "2") (pinfunction "2_2") (pintype "passive"))
      (node (ref "R7") (pin "1") (pinfunction "1_1") (pintype "passive"))
      (node (ref "T2") (pin "3") (pinfunction "G_3") (pintype "passive"))
    )
    (net (code "70") (name "Net-(U7-55-RI)") (class "Default")
      (node (ref "RI") (pin "TP") (pinfunction "TP_TP") (pintype "input"))
      (node (ref "U7") (pin "P$55") (pinfunction "55-RI_P$55") (pintype "bidirectional"))
    )
    (net (code "71") (name "Net-(U7-57-CTS)") (class "Default")
      (node (ref "U7") (pin "P$57") (pinfunction "57-CTS_P$57") (pintype "bidirectional"))
      (node (ref "U7") (pin "P$58") (pinfunction "58-RTS_P$58") (pintype "bidirectional"))
    )
    (net (code "72") (name "PWRKEY") (class "Default")
      (node (ref "KEY") (pin "1") (pinfunction "1_1") (pintype "passive"))
      (node (ref "POWER") (pin "1") (pinfunction "1_1") (pintype "passive"))
      (node (ref "Q3") (pin "C") (pinfunction "C_C") (pintype "passive"))
      (node (ref "U7") (pin "P$18") (pinfunction "18-PWRKEY_P$18") (pintype "bidirectional"))
      (node (ref "U8") (pin "P$3") (pinfunction "K2_P$3") (pintype "bidirectional"))
    )
    (net (code "73") (name "RESET_ARDUINO") (class "Default")
      (node (ref "RESET") (pin "1") (pinfunction "1_1") (pintype "passive"))
      (node (ref "U14") (pin "1") (pinfunction "PC6(/RESET)_1") (pintype "bidirectional"))
    )
    (net (code "74") (name "SIM_CLK") (class "Default")
      (node (ref "RN3") (pin "3") (pinfunction "1_3") (pintype "passive"))
      (node (ref "U7") (pin "P$14") (pinfunction "14-SIM_CLK_P$14") (pintype "bidirectional"))
    )
    (net (code "75") (name "SIM_DATA") (class "Default")
      (node (ref "RN3") (pin "4") (pinfunction "1_4") (pintype "passive"))
      (node (ref "U7") (pin "P$13") (pinfunction "13-SIM_DATA_P$13") (pintype "bidirectional"))
    )
    (net (code "76") (name "SIM_RST") (class "Default")
      (node (ref "RN3") (pin "2") (pinfunction "1_2") (pintype "passive"))
      (node (ref "U7") (pin "P$15") (pinfunction "15-SIM_RST_P$15") (pintype "bidirectional"))
    )
    (net (code "77") (name "SIM_VDD") (class "Default")
      (node (ref "C9") (pin "1") (pinfunction "1_1") (pintype "passive"))
      (node (ref "U7") (pin "P$12") (pinfunction "12-SIM_VDD_P$12") (pintype "bidirectional"))
      (node (ref "U8") (pin "P$4") (pinfunction "K3_P$4") (pintype "bidirectional"))
      (node (ref "X3") (pin "C1") (pinfunction "1_C1") (pintype "passive"))
    )
    (net (code "78") (name "STATUS") (class "Default")
      (node (ref "RN2") (pin "7") (pinfunction "2_7") (pintype "passive"))
      (node (ref "U7") (pin "P$54") (pinfunction "54-STATUS_P$54") (pintype "bidirectional"))
    )
    (net (code "79") (name "VBATT") (class "Default")
      (node (ref "C1") (pin "1") (pinfunction "1_1") (pintype "passive"))
      (node (ref "C2") (pin "1") (pinfunction "1_1") (pintype "passive"))
      (node (ref "C3") (pin "1") (pinfunction "1_1") (pintype "passive"))
      (node (ref "C4") (pin "1") (pinfunction "1_1") (pintype "passive"))
      (node (ref "NET") (pin "A") (pinfunction "A_A") (pintype "passive"))
      (node (ref "PC1") (pin "+") (pinfunction "+_+") (pintype "passive"))
      (node (ref "R2") (pin "2") (pinfunction "2_2") (pintype "passive"))
      (node (ref "R3") (pin "2") (pinfunction "2_2") (pintype "passive"))
      (node (ref "STA") (pin "A") (pinfunction "A_A") (pintype "passive"))
      (node (ref "U6") (pin "7") (pinfunction "VOUT_7") (pintype "power_in"))
      (node (ref "U7") (pin "P$50") (pinfunction "50-VBAT1_P$50") (pintype "bidirectional"))
      (node (ref "U7") (pin "P$51") (pinfunction "51-VBAT2_P$51") (pintype "bidirectional"))
      (node (ref "U7") (pin "P$52") (pinfunction "52-VBAT3_P$52") (pintype "bidirectional"))
      (node (ref "V1") (pin "TP") (pinfunction "TP_TP") (pintype "input"))
      (node (ref "V2") (pin "TP") (pinfunction "TP_TP") (pintype "input"))
      (node (ref "V3") (pin "TP") (pinfunction "TP_TP") (pintype "input"))
    )
    (net (code "80") (name "unconnected-(JP2-Pad3)") (class "Default")
      (node (ref "JP2") (pin "3") (pinfunction "3_3") (pintype "passive"))
    )
    (net (code "81") (name "unconnected-(U$1-Pad2)") (class "Default")
      (node (ref "U$1") (pin "2") (pinfunction "2_2") (pintype "bidirectional"))
    )
    (net (code "82") (name "unconnected-(U$1-Pad4)") (class "Default")
      (node (ref "U$1") (pin "4") (pinfunction "4_4") (pintype "bidirectional"))
    )
    (net (code "83") (name "unconnected-(U1-EPAD-Pad7)") (class "Default")
      (node (ref "U1") (pin "7") (pinfunction "EPAD_7") (pintype "passive"))
    )
    (net (code "84") (name "unconnected-(U1-NC-Pad3)") (class "Default")
      (node (ref "U1") (pin "3") (pinfunction "NC_3") (pintype "no_connect"))
    )
    (net (code "85") (name "unconnected-(U1-NC_2-Pad4)") (class "Default")
      (node (ref "U1") (pin "4") (pinfunction "NC_2_4") (pintype "no_connect"))
    )
    (net (code "86") (name "unconnected-(U7-7-VDD_EXT-PadP$7)") (class "Default")
      (node (ref "U7") (pin "P$7") (pinfunction "7-VDD_EXT_P$7") (pintype "bidirectional"))
    )
    (net (code "87") (name "unconnected-(U7-11-SIM_PRESENCE-PadP$11)") (class "Default")
      (node (ref "U7") (pin "P$11") (pinfunction "11-SIM_PRESENCE_P$11") (pintype "bidirectional"))
    )
    (net (code "88") (name "unconnected-(U7-17-EMERG_OFF-PadP$17)") (class "Default")
      (node (ref "U7") (pin "P$17") (pinfunction "17-EMERG_OFF_P$17") (pintype "bidirectional"))
    )
    (net (code "89") (name "unconnected-(U7-40-TEMP_BAT-PadP$40)") (class "Default")
      (node (ref "U7") (pin "P$40") (pinfunction "40-TEMP_BAT_P$40") (pintype "bidirectional"))
    )
    (net (code "90") (name "unconnected-(U7-53-VCHG-PadP$53)") (class "Default")
      (node (ref "U7") (pin "P$53") (pinfunction "53-VCHG_P$53") (pintype "bidirectional"))
    )
    (net (code "91") (name "unconnected-(U7-56-DCD-PadP$56)") (class "Default")
      (node (ref "U7") (pin "P$56") (pinfunction "56-DCD_P$56") (pintype "bidirectional"))
    )
    (net (code "92") (name "unconnected-(U7-62-TXD3-PadP$62)") (class "Default")
      (node (ref "U7") (pin "P$62") (pinfunction "62-TXD3_P$62") (pintype "bidirectional"))
    )
    (net (code "93") (name "unconnected-(U7-63-RXD3-PadP$63)") (class "Default")
      (node (ref "U7") (pin "P$63") (pinfunction "63-RXD3_P$63") (pintype "bidirectional"))
    )
    (net (code "94") (name "unconnected-(U14-AREF-Pad21)") (class "Default")
      (node (ref "U14") (pin "21") (pinfunction "AREF_21") (pintype "bidirectional"))
    )
    (net (code "95") (name "unconnected-(U14-GND-Pad22)") (class "Default")
      (node (ref "U14") (pin "22") (pinfunction "GND_22") (pintype "bidirectional"))
    )
    (net (code "96") (name "unconnected-(U14-PB0(ICP)-Pad14)") (class "Default")
      (node (ref "U14") (pin "14") (pinfunction "PB0(ICP)_14") (pintype "bidirectional"))
    )
    (net (code "97") (name "unconnected-(U14-PB1(OC1A)-Pad15)") (class "Default")
      (node (ref "U14") (pin "15") (pinfunction "PB1(OC1A)_15") (pintype "bidirectional"))
    )
    (net (code "98") (name "unconnected-(U14-PB2(SS{slash}OC1B)-Pad16)") (class "Default")
      (node (ref "U14") (pin "16") (pinfunction "PB2(SS/OC1B)_16") (pintype "bidirectional"))
    )
    (net (code "99") (name "unconnected-(U14-PB3(MOSI{slash}OC2)-Pad17)") (class "Default")
      (node (ref "U14") (pin "17") (pinfunction "PB3(MOSI/OC2)_17") (pintype "bidirectional"))
    )
    (net (code "100") (name "unconnected-(U14-PB4(MISO)-Pad18)") (class "Default")
      (node (ref "U14") (pin "18") (pinfunction "PB4(MISO)_18") (pintype "bidirectional"))
    )
    (net (code "101") (name "unconnected-(U14-PB5(SCK)-Pad19)") (class "Default")
      (node (ref "U14") (pin "19") (pinfunction "PB5(SCK)_19") (pintype "bidirectional"))
    )
    (net (code "102") (name "unconnected-(U14-PB6(XTAL1{slash}TOSC1)-Pad9)") (class "Default")
      (node (ref "U14") (pin "9") (pinfunction "PB6(XTAL1/TOSC1)_9") (pintype "bidirectional"))
    )
    (net (code "103") (name "unconnected-(U14-PB7(XTAL2{slash}TOSC2)-Pad10)") (class "Default")
      (node (ref "U14") (pin "10") (pinfunction "PB7(XTAL2/TOSC2)_10") (pintype "bidirectional"))
    )
    (net (code "104") (name "unconnected-(U14-PC1(ADC1)-Pad24)") (class "Default")
      (node (ref "U14") (pin "24") (pinfunction "PC1(ADC1)_24") (pintype "bidirectional"))
    )
    (net (code "105") (name "unconnected-(U14-PC2(ADC2)-Pad25)") (class "Default")
      (node (ref "U14") (pin "25") (pinfunction "PC2(ADC2)_25") (pintype "bidirectional"))
    )
    (net (code "106") (name "unconnected-(U14-PC3(ADC3)-Pad26)") (class "Default")
      (node (ref "U14") (pin "26") (pinfunction "PC3(ADC3)_26") (pintype "bidirectional"))
    )
    (net (code "107") (name "unconnected-(U14-PD2(INT0)-Pad4)") (class "Default")
      (node (ref "U14") (pin "4") (pinfunction "PD2(INT0)_4") (pintype "bidirectional"))
    )
    (net (code "108") (name "unconnected-(U14-PD3(INT1)-Pad5)") (class "Default")
      (node (ref "U14") (pin "5") (pinfunction "PD3(INT1)_5") (pintype "bidirectional"))
    )
    (net (code "109") (name "unconnected-(U14-PD4(XCK{slash}T0)-Pad6)") (class "Default")
      (node (ref "U14") (pin "6") (pinfunction "PD4(XCK/T0)_6") (pintype "bidirectional"))
    )
    (net (code "110") (name "unconnected-(U14-PD5(T1)-Pad11)") (class "Default")
      (node (ref "U14") (pin "11") (pinfunction "PD5(T1)_11") (pintype "bidirectional"))
    )
    (net (code "111") (name "unconnected-(U14-PD6(AIN0)-Pad12)") (class "Default")
      (node (ref "U14") (pin "12") (pinfunction "PD6(AIN0)_12") (pintype "bidirectional"))
    )
    (net (code "112") (name "unconnected-(X3-5-PadC6)") (class "Default")
      (node (ref "X3") (pin "C6") (pinfunction "5_C6") (pintype "passive"))
    )
  )
)
